# signal_circuit_Sch.net
KiCad netlist of a schematic drawn in Altium Designer
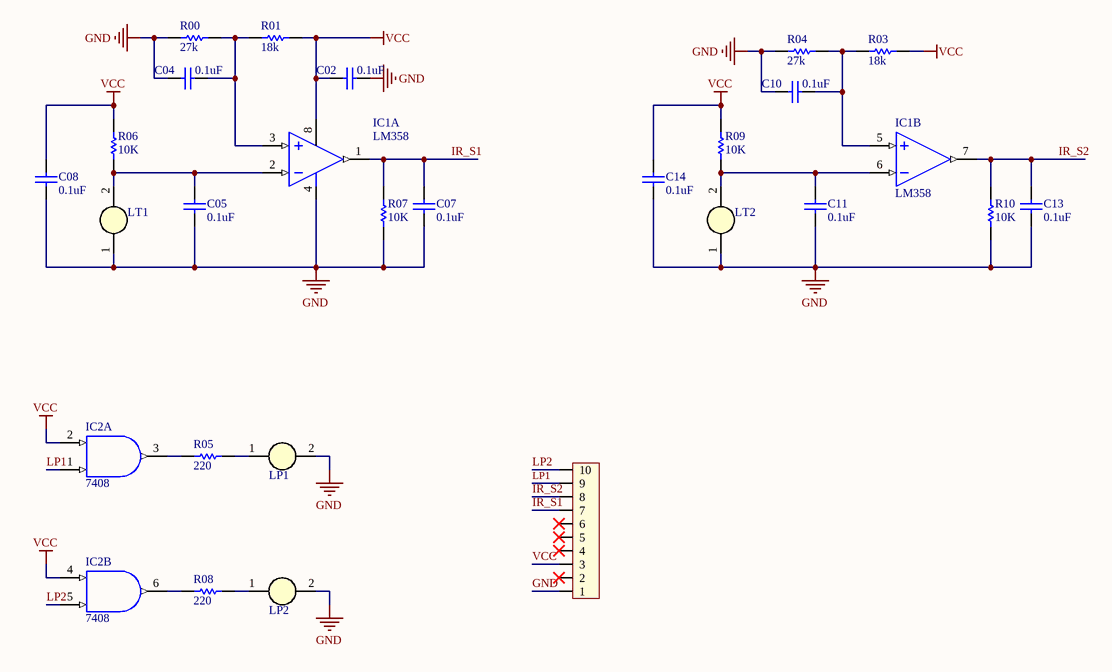
[diagram p0: signal_circuit_Sch.SchDoc]

(export (version "E")
  (design (tool "Eeschema 10.0.6"))
  (components
    (comp (ref "C02")
      (value "0.1uF")
      (footprint "CAP-SM-0603")
      (description "Capacitor")
      (fields (field (name "Comment") "Cap Non-Pol SMD"))
      (libsource (lib "PIF_Library") (part "Cap Non-Pol SMD"))
    )
    (comp (ref "C04")
      (value "0.1uF")
      (footprint "CAP-SM-0603")
      (description "Capacitor")
      (fields (field (name "Comment") "Cap Non-Pol SMD"))
      (libsource (lib "PIF_Library") (part "Cap Non-Pol SMD"))
    )
    (comp (ref "C05")
      (value "0.1uF")
      (footprint "CAP-SM-0603")
      (description "Capacitor")
      (fields (field (name "Comment") "Cap Non-Pol SMD"))
      (libsource (lib "PIF_Library") (part "Cap Non-Pol SMD"))
    )
    (comp (ref "C07")
      (value "0.1uF")
      (footprint "CAP-SM-0603")
      (description "Capacitor")
      (fields (field (name "Comment") "Cap Non-Pol SMD"))
      (libsource (lib "PIF_Library") (part "Cap Non-Pol SMD"))
    )
    (comp (ref "C08")
      (value "0.1uF")
      (footprint "CAP-SM-0603")
      (description "Capacitor")
      (fields (field (name "Comment") "Cap Non-Pol SMD"))
      (libsource (lib "PIF_Library") (part "Cap Non-Pol SMD"))
    )
    (comp (ref "C10")
      (value "0.1uF")
      (footprint "CAP-SM-0603")
      (description "Capacitor")
      (fields (field (name "Comment") "Cap Non-Pol SMD"))
      (libsource (lib "PIF_Library") (part "Cap Non-Pol SMD"))
    )
    (comp (ref "C11")
      (value "0.1uF")
      (footprint "CAP-SM-0603")
      (description "Capacitor")
      (fields (field (name "Comment") "Cap Non-Pol SMD"))
      (libsource (lib "PIF_Library") (part "Cap Non-Pol SMD"))
    )
    (comp (ref "C13")
      (value "0.1uF")
      (footprint "CAP-SM-0603")
      (description "Capacitor")
      (fields (field (name "Comment") "Cap Non-Pol SMD"))
      (libsource (lib "PIF_Library") (part "Cap Non-Pol SMD"))
    )
    (comp (ref "C14")
      (value "0.1uF")
      (footprint "CAP-SM-0603")
      (description "Capacitor")
      (fields (field (name "Comment") "Cap Non-Pol SMD"))
      (libsource (lib "PIF_Library") (part "Cap Non-Pol SMD"))
    )
    (comp (ref "H0")
      (value "RIGHT")
      (footprint "XH2.54M-10")
      (description "Cắm")
      (libsource (lib "Altium_Lib_by_KhueNguyenCreator") (part "Header 10P 2.54 Duc Thang"))
    )
    (comp (ref "IC1")
      (value "LM358")
      (footprint "SO8")
      (description "Low-Power Dual Operational Amplifier")
      (libsource (lib "TechMT.VN_Lib_Project v2") (part "LM358"))
    )
    (comp (ref "IC2")
      (value "7408")
      (footprint "SO14")
      (description "Quad 2-Input AND Gate")
      (libsource (lib "") (part "7408_1"))
    )
    (comp (ref "LP1")
      (value "LED 5mm")
      (footprint "LED-5MM-WHITE")
      (description "Cắm")
      (libsource (lib "Altium_Lib_by_KhueNguyenCreator") (part "LED 5mm Trang"))
    )
    (comp (ref "LP2")
      (value "LED 5mm")
      (footprint "LED-5MM-WHITE")
      (description "Cắm")
      (libsource (lib "Altium_Lib_by_KhueNguyenCreator") (part "LED 5mm Trang"))
    )
    (comp (ref "LT1")
      (value "LED 5mm")
      (footprint "LED-5MM-WHITE")
      (description "Cắm")
      (libsource (lib "Altium_Lib_by_KhueNguyenCreator") (part "LED 5mm Trang"))
    )
    (comp (ref "LT2")
      (value "LED 5mm")
      (footprint "LED-5MM-WHITE")
      (description "Cắm")
      (libsource (lib "Altium_Lib_by_KhueNguyenCreator") (part "LED 5mm Trang"))
    )
    (comp (ref "R00")
      (value "27k")
      (footprint "RES-SM-0603")
      (description "Resistor")
      (fields (field (name "Comment") "RESISTOR SMD"))
      (libsource (lib "PIF_Library") (part "RESISTOR SMD"))
    )
    (comp (ref "R01")
      (value "18k")
      (footprint "RES-SM-0603")
      (description "Resistor")
      (fields (field (name "Comment") "RESISTOR SMD"))
      (libsource (lib "PIF_Library") (part "RESISTOR SMD"))
    )
    (comp (ref "R03")
      (value "18k")
      (footprint "RES-SM-0603")
      (description "Resistor")
      (fields (field (name "Comment") "RESISTOR SMD"))
      (libsource (lib "PIF_Library") (part "RESISTOR SMD"))
    )
    (comp (ref "R04")
      (value "27k")
      (footprint "RES-SM-0603")
      (description "Resistor")
      (fields (field (name "Comment") "RESISTOR SMD"))
      (libsource (lib "PIF_Library") (part "RESISTOR SMD"))
    )
    (comp (ref "R05")
      (value "220")
      (footprint "RES-SM-0603")
      (description "Resistor")
      (fields (field (name "Comment") "RESISTOR SMD"))
      (libsource (lib "PIF_Library") (part "RESISTOR SMD"))
    )
    (comp (ref "R06")
      (value "10K")
      (footprint "RES-SM-0603")
      (description "Resistor")
      (fields (field (name "Comment") "RESISTOR SMD"))
      (libsource (lib "PIF_Library") (part "RESISTOR SMD"))
    )
    (comp (ref "R07")
      (value "10K")
      (footprint "RES-SM-0603")
      (description "Resistor")
      (fields (field (name "Comment") "RESISTOR SMD"))
      (libsource (lib "PIF_Library") (part "RESISTOR SMD"))
    )
    (comp (ref "R08")
      (value "220")
      (footprint "RES-SM-0603")
      (description "Resistor")
      (fields (field (name "Comment") "RESISTOR SMD"))
      (libsource (lib "PIF_Library") (part "RESISTOR SMD"))
    )
    (comp (ref "R09")
      (value "10K")
      (footprint "RES-SM-0603")
      (description "Resistor")
      (fields (field (name "Comment") "RESISTOR SMD"))
      (libsource (lib "PIF_Library") (part "RESISTOR SMD"))
    )
    (comp (ref "R10")
      (value "10K")
      (footprint "RES-SM-0603")
      (description "Resistor")
      (fields (field (name "Comment") "RESISTOR SMD"))
      (libsource (lib "PIF_Library") (part "RESISTOR SMD"))
    )
  )
  (nets
    (net (code "1") (name "/IR_S1") (class "Default")
      (node (ref "C07") (pin "1") (pinfunction "1_1") (pintype "passive"))
      (node (ref "H0") (pin "7") (pinfunction "7_7") (pintype "passive"))
      (node (ref "IC1") (pin "1") (pinfunction "OUT_1") (pintype "output"))
      (node (ref "R07") (pin "2") (pinfunction "2_2") (pintype "passive"))
    )
    (net (code "2") (name "/IR_S2") (class "Default")
      (node (ref "C13") (pin "1") (pinfunction "1_1") (pintype "passive"))
      (node (ref "H0") (pin "8") (pinfunction "8_8") (pintype "passive"))
      (node (ref "IC1") (pin "7") (pinfunction "OUT_7") (pintype "output"))
      (node (ref "R10") (pin "2") (pinfunction "2_2") (pintype "passive"))
    )
    (net (code "3") (name "/LP1") (class "Default")
      (node (ref "H0") (pin "9") (pinfunction "9_9") (pintype "passive"))
      (node (ref "IC2") (pin "1") (pinfunction "A_1") (pintype "input"))
    )
    (net (code "4") (name "/LP2") (class "Default")
      (node (ref "H0") (pin "10") (pinfunction "10_10") (pintype "passive"))
      (node (ref "IC2") (pin "5") (pinfunction "B_5") (pintype "input"))
    )
    (net (code "5") (name "GND") (class "Default")
      (node (ref "C02") (pin "2") (pinfunction "2_2") (pintype "passive"))
      (node (ref "C04") (pin "1") (pinfunction "1_1") (pintype "passive"))
      (node (ref "C05") (pin "2") (pinfunction "2_2") (pintype "passive"))
      (node (ref "C07") (pin "2") (pinfunction "2_2") (pintype "passive"))
      (node (ref "C08") (pin "2") (pinfunction "2_2") (pintype "passive"))
      (node (ref "C10") (pin "2") (pinfunction "2_2") (pintype "passive"))
      (node (ref "C11") (pin "2") (pinfunction "2_2") (pintype "passive"))
      (node (ref "C13") (pin "2") (pinfunction "2_2") (pintype "passive"))
      (node (ref "C14") (pin "2") (pinfunction "2_2") (pintype "passive"))
      (node (ref "H0") (pin "1") (pinfunction "1_1") (pintype "passive"))
      (node (ref "IC1") (pin "4") (pinfunction "-V_4") (pintype "passive"))
      (node (ref "IC2") (pin "7") (pinfunction "GND_7") (pintype "power_in"))
      (node (ref "LP1") (pin "2") (pinfunction "K_2") (pintype "passive"))
      (node (ref "LP2") (pin "2") (pinfunction "K_2") (pintype "passive"))
      (node (ref "LT1") (pin "1") (pinfunction "A_1") (pintype "passive"))
      (node (ref "LT2") (pin "1") (pinfunction "A_1") (pintype "passive"))
      (node (ref "R00") (pin "1") (pinfunction "1_1") (pintype "passive"))
      (node (ref "R04") (pin "1") (pinfunction "1_1") (pintype "passive"))
      (node (ref "R07") (pin "1") (pinfunction "1_1") (pintype "passive"))
      (node (ref "R10") (pin "1") (pinfunction "1_1") (pintype "passive"))
    )
    (net (code "6") (name "Net-(IC1A-IN+)") (class "Default")
      (node (ref "C04") (pin "2") (pinfunction "2_2") (pintype "passive"))
      (node (ref "IC1") (pin "3") (pinfunction "IN+_3") (pintype "input"))
      (node (ref "R00") (pin "2") (pinfunction "2_2") (pintype "passive"))
      (node (ref "R01") (pin "1") (pinfunction "1_1") (pintype "passive"))
    )
    (net (code "7") (name "Net-(IC1A-IN-)") (class "Default")
      (node (ref "C05") (pin "1") (pinfunction "1_1") (pintype "passive"))
      (node (ref "IC1") (pin "2") (pinfunction "IN-_2") (pintype "input"))
      (node (ref "LT1") (pin "2") (pinfunction "K_2") (pintype "passive"))
      (node (ref "R06") (pin "1") (pinfunction "1_1") (pintype "passive"))
    )
    (net (code "8") (name "Net-(IC1B-IN+)") (class "Default")
      (node (ref "C10") (pin "1") (pinfunction "1_1") (pintype "passive"))
      (node (ref "IC1") (pin "5") (pinfunction "IN+_5") (pintype "input"))
      (node (ref "R03") (pin "1") (pinfunction "1_1") (pintype "passive"))
      (node (ref "R04") (pin "2") (pinfunction "2_2") (pintype "passive"))
    )
    (net (code "9") (name "Net-(IC1B-IN-)") (class "Default")
      (node (ref "C11") (pin "1") (pinfunction "1_1") (pintype "passive"))
      (node (ref "IC1") (pin "6") (pinfunction "IN-_6") (pintype "input"))
      (node (ref "LT2") (pin "2") (pinfunction "K_2") (pintype "passive"))
      (node (ref "R09") (pin "1") (pinfunction "1_1") (pintype "passive"))
    )
    (net (code "10") (name "Net-(IC2A-O)") (class "Default")
      (node (ref "IC2") (pin "3") (pinfunction "O_3") (pintype "output"))
      (node (ref "R05") (pin "2") (pinfunction "2_2") (pintype "passive"))
    )
    (net (code "11") (name "Net-(IC2B-O)") (class "Default")
      (node (ref "IC2") (pin "6") (pinfunction "O_6") (pintype "output"))
      (node (ref "R08") (pin "2") (pinfunction "2_2") (pintype "passive"))
    )
    (net (code "12") (name "Net-(LP1-A)") (class "Default")
      (node (ref "LP1") (pin "1") (pinfunction "A_1") (pintype "passive"))
      (node (ref "R05") (pin "1") (pinfunction "1_1") (pintype "passive"))
    )
    (net (code "13") (name "Net-(LP2-A)") (class "Default")
      (node (ref "LP2") (pin "1") (pinfunction "A_1") (pintype "passive"))
      (node (ref "R08") (pin "1") (pinfunction "1_1") (pintype "passive"))
    )
    (net (code "14") (name "VCC") (class "Default")
      (node (ref "C02") (pin "1") (pinfunction "1_1") (pintype "passive"))
      (node (ref "C08") (pin "1") (pinfunction "1_1") (pintype "passive"))
      (node (ref "C14") (pin "1") (pinfunction "1_1") (pintype "passive"))
      (node (ref "H0") (pin "3") (pinfunction "3_3") (pintype "passive"))
      (node (ref "IC1") (pin "8") (pinfunction "+V_8") (pintype "passive"))
      (node (ref "IC2") (pin "14") (pinfunction "VCC_14") (pintype "power_in"))
      (node (ref "IC2") (pin "2") (pinfunction "B_2") (pintype "input"))
      (node (ref "IC2") (pin "4") (pinfunction "A_4") (pintype "input"))
      (node (ref "R01") (pin "2") (pinfunction "2_2") (pintype "passive"))
      (node (ref "R03") (pin "2") (pinfunction "2_2") (pintype "passive"))
      (node (ref "R06") (pin "2") (pinfunction "2_2") (pintype "passive"))
      (node (ref "R09") (pin "2") (pinfunction "2_2") (pintype "passive"))
    )
    (net (code "15") (name "unconnected-(H0-Pad2)") (class "Default")
      (node (ref "H0") (pin "2") (pinfunction "2_2") (pintype "passive+no_connect"))
    )
    (net (code "16") (name "unconnected-(H0-Pad4)") (class "Default")
      (node (ref "H0") (pin "4") (pinfunction "4_4") (pintype "passive+no_connect"))
    )
    (net (code "17") (name "unconnected-(H0-Pad5)") (class "Default")
      (node (ref "H0") (pin "5") (pinfunction "5_5") (pintype "passive+no_connect"))
    )
    (net (code "18") (name "unconnected-(H0-Pad6)") (class "Default")
      (node (ref "H0") (pin "6") (pinfunction "6_6") (pintype "passive+no_connect"))
    )
  )
)
